# GPS.net
KiCad netlist of a schematic drawn in Altium Designer
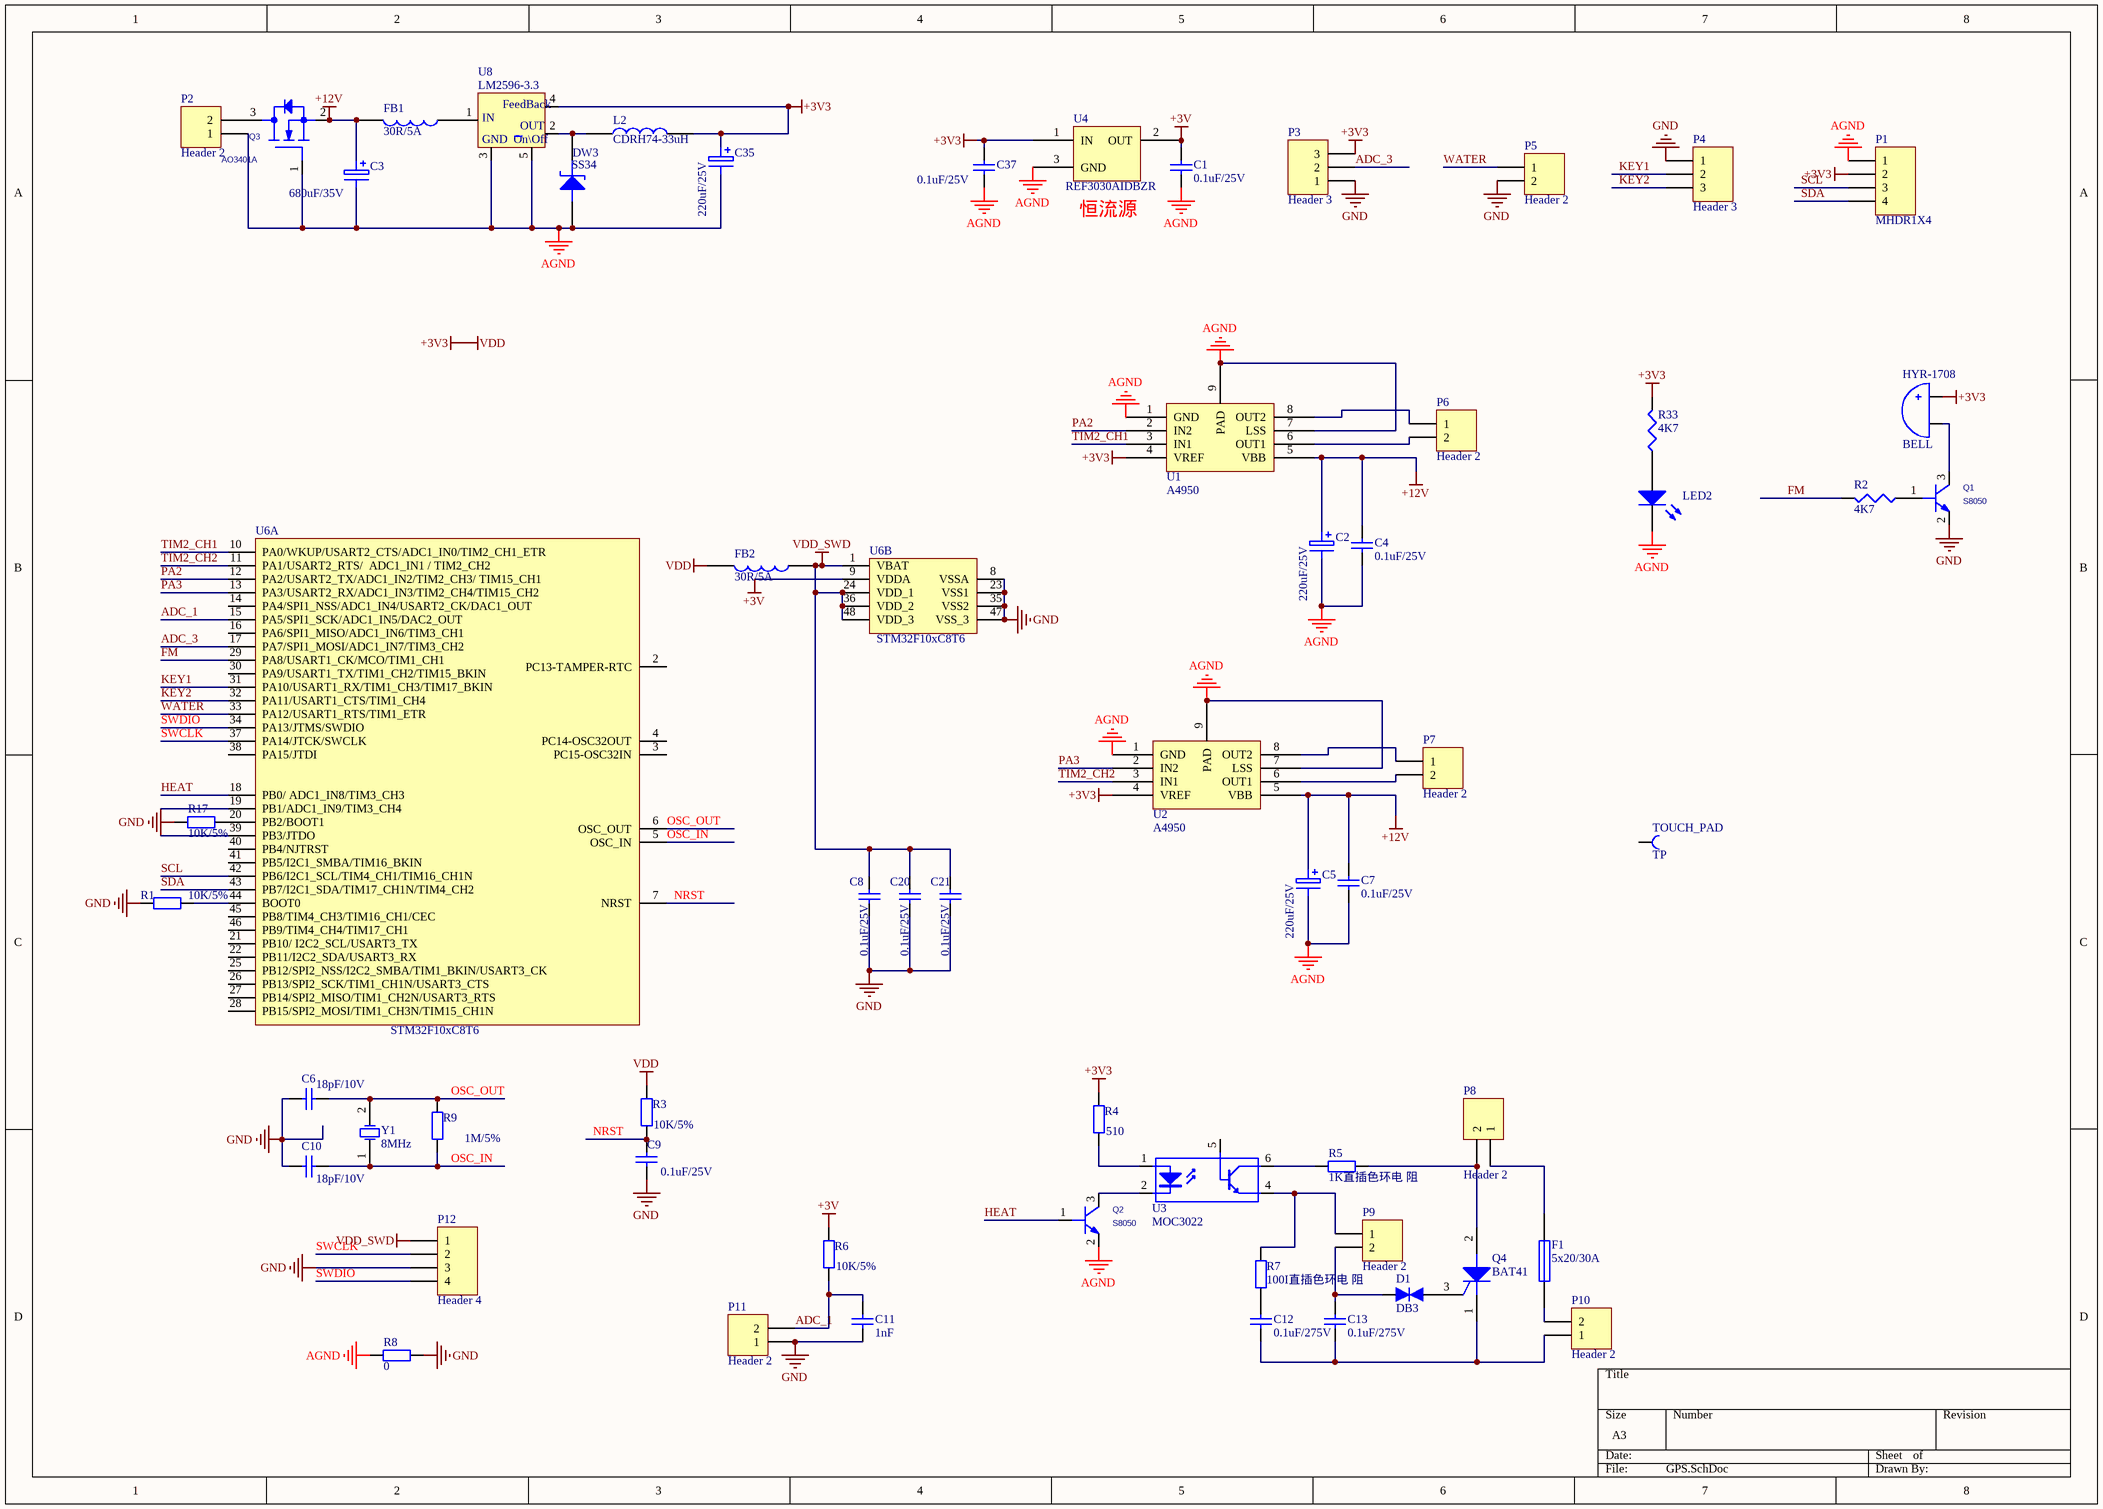
[diagram p0: GPS.SchDoc]

(export (version "E")
  (design (tool "Eeschema 10.0.6"))
  (components
    (comp (ref "C1")
      (value "0.1uF/25V")
      (footprint "0603C")
      (description "Capacitor")
      (fields (field (name "PUBLISHER") "Altium Limited"))
      (libsource (lib "Miscellaneous Devices") (part "Cap"))
    )
    (comp (ref "C2") (value "220uF/25V") (footprint "CAP 2.5*6.3*11.2") (libsource (lib "*") (part "E01")))
    (comp (ref "C3") (value "680uF/35V") (footprint "CAP 5.0*10*16") (libsource (lib "*") (part "E01")))
    (comp (ref "C4")
      (value "0.1uF/25V")
      (footprint "0603C")
      (description "Capacitor")
      (fields (field (name "PUBLISHER") "Altium Limited"))
      (libsource (lib "Miscellaneous Devices") (part "Cap"))
    )
    (comp (ref "C5") (value "220uF/25V") (footprint "CAP 2.5*6.3*11.2") (libsource (lib "*") (part "E01")))
    (comp (ref "C6")
      (value "18pF/10V")
      (footprint "0603C")
      (description "Capacitor")
      (fields (field (name "PUBLISHER") "Altium Limited"))
      (libsource (lib "Miscellaneous Devices") (part "Cap"))
    )
    (comp (ref "C7")
      (value "0.1uF/25V")
      (footprint "0603C")
      (description "Capacitor")
      (fields (field (name "PUBLISHER") "Altium Limited"))
      (libsource (lib "Miscellaneous Devices") (part "Cap"))
    )
    (comp (ref "C8")
      (value "0.1uF/25V")
      (footprint "0603C")
      (description "Capacitor")
      (fields (field (name "PUBLISHER") "Altium Limited"))
      (libsource (lib "Miscellaneous Devices") (part "Cap"))
    )
    (comp (ref "C9")
      (value "0.1uF/25V")
      (footprint "0603c")
      (description "Capacitor")
      (fields (field (name "PUBLISHER") "Altium Limited"))
      (libsource (lib "Miscellaneous Devices") (part "Cap"))
    )
    (comp (ref "C10")
      (value "18pF/10V")
      (footprint "0603c")
      (description "Capacitor")
      (fields (field (name "PUBLISHER") "Altium Limited"))
      (libsource (lib "Miscellaneous Devices") (part "Cap"))
    )
    (comp (ref "C11")
      (value "1nF")
      (footprint "0603C")
      (description "Capacitor")
      (fields (field (name "PUBLISHER") "Altium Limited"))
      (libsource (lib "Miscellaneous Devices") (part "Cap"))
    )
    (comp (ref "C12")
      (value "0.1uF/275V")
      (footprint "CBB 10*12*8")
      (description "Capacitor")
      (fields (field (name "PUBLISHER") "Altium Limited"))
      (libsource (lib "Miscellaneous Devices") (part "Cap"))
    )
    (comp (ref "C13")
      (value "0.1uF/275V")
      (footprint "CBB 10*12*8")
      (description "Capacitor")
      (fields (field (name "PUBLISHER") "Altium Limited"))
      (libsource (lib "Miscellaneous Devices") (part "Cap"))
    )
    (comp (ref "C20")
      (value "0.1uF/25V")
      (footprint "0603C")
      (description "Capacitor")
      (fields (field (name "PUBLISHER") "Altium Limited"))
      (libsource (lib "Miscellaneous Devices") (part "Cap"))
    )
    (comp (ref "C21")
      (value "0.1uF/25V")
      (footprint "0603C")
      (description "Capacitor")
      (fields (field (name "PUBLISHER") "Altium Limited"))
      (libsource (lib "Miscellaneous Devices") (part "Cap"))
    )
    (comp (ref "C35") (value "220uF/25V") (footprint "CAP 2.5*6.3*11.2") (libsource (lib "*") (part "E01")))
    (comp (ref "C37")
      (value "0.1uF/25V")
      (footprint "0603C")
      (description "Capacitor")
      (fields (field (name "PUBLISHER") "Altium Limited"))
      (libsource (lib "Miscellaneous Devices") (part "Cap"))
    )
    (comp (ref "D1")
      (value "DB3")
      (footprint "DO-35")
      (libsource (lib "Schlib_20110825") (part "ESD9M5.0S-DTVS105"))
    )
    (comp (ref "DW3")
      (value "SS34")
      (footprint "SMA")
      (description "Zener Diode")
      (libsource (lib "MySchlib") (part "ZENER2"))
    )
    (comp (ref "F1")
      (value "5x20/30A")
      (footprint "FU BLX-A")
      (description "Fuse")
      (fields (field (name "PUBLISHER") "Altium Limited"))
      (libsource (lib "Miscellaneous Devices") (part "Fuse 1"))
    )
    (comp (ref "FB1") (value "30R/5A") (footprint "L 0805") (libsource (lib "*") (part "INDUCTOR1")))
    (comp (ref "FB2") (value "30R/5A") (footprint "L 0805") (libsource (lib "*") (part "INDUCTOR1")))
    (comp (ref "HYR-1708")
      (value "BELL")
      (footprint "BEEP 5x9x5.5")
      (description "Bell")
      (libsource (lib "*") (part "BELL"))
    )
    (comp (ref "L2") (value "CDRH74-33uH") (footprint "CDRH74") (libsource (lib "*") (part "INDUCTOR1")))
    (comp (ref "LED2")
      (value "~")
      (footprint "LED 0805R")
      (description "Typical INFRARED GaAs LED")
      (fields (field (name "PUBLISHER") "Altium Limited"))
      (libsource (lib "Miscellaneous Devices") (part "LED0"))
    )
    (comp (ref "P1")
      (value "MHDR1X4")
      (footprint "MX 1.25-LS-4P")
      (description "Header, 4-Pin")
      (fields (field (name "PUBLISHER") "Altium Limited"))
      (libsource (lib "Miscellaneous Connectors") (part "MHDR1X4"))
    )
    (comp (ref "P2")
      (value "Header 2")
      (footprint "VH3.96-LI-2P")
      (description "Header, 2-Pin")
      (fields (field (name "PUBLISHER") "Altium Limited"))
      (libsource (lib "") (part "Header 2_2"))
    )
    (comp (ref "P3")
      (value "Header 3")
      (footprint "XH2.54-LI-3P")
      (description "Header, 3-Pin")
      (fields (field (name "PUBLISHER") "Altium Limited"))
      (libsource (lib "Miscellaneous Connectors") (part "Header 3"))
    )
    (comp (ref "P4")
      (value "Header 3")
      (footprint "MX 1.25-LS-3P")
      (description "Header, 3-Pin")
      (fields (field (name "PUBLISHER") "Altium Limited"))
      (libsource (lib "") (part "Header 3_1"))
    )
    (comp (ref "P5")
      (value "Header 2")
      (footprint "PH2.0-LS-2P")
      (description "Header, 2-Pin")
      (fields (field (name "PUBLISHER") "Altium Limited"))
      (libsource (lib "") (part "Header 2_1"))
    )
    (comp (ref "P6")
      (value "Header 2")
      (footprint "XH2.54-LI-2P")
      (description "Header, 2-Pin")
      (fields (field (name "PUBLISHER") "Altium Limited"))
      (libsource (lib "") (part "Header 2_1"))
    )
    (comp (ref "P7")
      (value "Header 2")
      (footprint "XH2.54-LI-2P")
      (description "Header, 2-Pin")
      (fields (field (name "PUBLISHER") "Altium Limited"))
      (libsource (lib "") (part "Header 2_1"))
    )
    (comp (ref "P8")
      (value "Header 2")
      (footprint "KF2EDGK5.08-LI-2P")
      (description "Header, 2-Pin")
      (fields (field (name "PUBLISHER") "Altium Limited"))
      (libsource (lib "") (part "Header 2_1"))
    )
    (comp (ref "P9")
      (value "Header 2")
      (footprint "VH3.96-LI-2P")
      (description "Header, 2-Pin")
      (fields (field (name "PUBLISHER") "Altium Limited"))
      (libsource (lib "") (part "Header 2_1"))
    )
    (comp (ref "P10")
      (value "Header 2")
      (footprint "KF2EDGK5.08-LI-2P")
      (description "Header, 2-Pin")
      (fields (field (name "PUBLISHER") "Altium Limited"))
      (libsource (lib "Miscellaneous Connectors") (part "Header 2"))
    )
    (comp (ref "P11")
      (value "Header 2")
      (footprint "XH2.54-LI-2P")
      (description "Header, 2-Pin")
      (fields (field (name "PUBLISHER") "Altium Limited"))
      (libsource (lib "") (part "Header 2_2"))
    )
    (comp (ref "P12")
      (value "Header 4")
      (footprint "HDR1X4")
      (description "Header, 4-Pin")
      (fields (field (name "PUBLISHER") "Altium Limited"))
      (libsource (lib "Miscellaneous Connectors") (part "Header 4"))
    )
    (comp (ref "Q1") (value "S8050") (footprint "SOT23-3") (libsource (lib "*") (part "2N1069_1")))
    (comp (ref "Q2") (value "S8050") (footprint "SOT23-3") (libsource (lib "*") (part "2N1069_1")))
    (comp (ref "Q3") (value "AO3401A") (footprint "SOT23-3M") (libsource (lib "Ground_Lock") (part "NMOS")))
    (comp (ref "Q4")
      (value "BAT41")
      (footprint "TOP-3")
      (description "Silicon Controlled Rectifier")
      (fields (field (name "PUBLISHER") "Altium Limited"))
      (libsource (lib "Miscellaneous Devices") (part "SCR"))
    )
    (comp (ref "R1")
      (value "10K/5%")
      (footprint "0603r")
      (description "Resistor")
      (fields (field (name "PUBLISHER") "Altium Limited"))
      (libsource (lib "") (part "Res2_1"))
    )
    (comp (ref "R2")
      (value "4K7")
      (footprint "0603R")
      (libsource (lib "ZWLIntegrated_Library") (part "RES1"))
    )
    (comp (ref "R3")
      (value "10K/5%")
      (footprint "0603r")
      (description "Resistor")
      (fields (field (name "PUBLISHER") "Altium Limited"))
      (libsource (lib "Miscellaneous Devices") (part "Res2"))
    )
    (comp (ref "R4")
      (value "510")
      (footprint "0603r")
      (description "Resistor")
      (fields (field (name "PUBLISHER") "Altium Limited"))
      (libsource (lib "Miscellaneous Devices") (part "Res2"))
    )
    (comp (ref "R5")
      (value "1K直插色环电 阻")
      (footprint "RS 1W")
      (description "Resistor")
      (fields (field (name "PUBLISHER") "Altium Limited"))
      (libsource (lib "") (part "Res2_1"))
    )
    (comp (ref "R6")
      (value "10K/5%")
      (footprint "0603r")
      (description "Resistor")
      (fields (field (name "PUBLISHER") "Altium Limited"))
      (libsource (lib "Miscellaneous Devices") (part "Res2"))
    )
    (comp (ref "R7")
      (value "100I直插色环电 阻")
      (footprint "RS 1W")
      (description "Resistor")
      (fields (field (name "PUBLISHER") "Altium Limited"))
      (libsource (lib "") (part "Res2_2"))
    )
    (comp (ref "R8")
      (value "0")
      (footprint "R 0805_M")
      (description "Resistor")
      (fields (field (name "PUBLISHER") "Altium Limited"))
      (libsource (lib "") (part "Res2_1"))
    )
    (comp (ref "R9")
      (value "1M/5%")
      (footprint "0603R")
      (description "Resistor")
      (fields (field (name "PUBLISHER") "Altium Limited"))
      (libsource (lib "Miscellaneous Devices") (part "Res2"))
    )
    (comp (ref "R17")
      (value "10K/5%")
      (footprint "0603r")
      (description "Resistor")
      (fields (field (name "PUBLISHER") "Altium Limited"))
      (libsource (lib "") (part "Res2_1"))
    )
    (comp (ref "R33")
      (value "4K7")
      (footprint "0603R")
      (libsource (lib "ZWLIntegrated_Library") (part "RES1"))
    )
    (comp (ref "TOUCH_PAD")
      (value "TP")
      (footprint "SRP12-34-25-P")
      (description "TEST_3P")
      (libsource (lib "stm32") (part "TOUCH_PAD"))
    )
    (comp (ref "U1")
      (value "A4950")
      (footprint "SOIC_8_EP")
      (libsource (lib "Schlib_20110825") (part "A4950"))
    )
    (comp (ref "U2")
      (value "A4950")
      (footprint "SOIC_8_EP")
      (libsource (lib "Schlib_20110825") (part "A4950"))
    )
    (comp (ref "U3")
      (value "MOC3022")
      (footprint "DIP6-300")
      (description "5 Pin Mini Flat Pack Optocoupler")
      (fields (field (name "PUBLISHER") "Altium Limited"))
      (libsource (lib "Miscellaneous Devices") (part "Optoisolator2"))
    )
    (comp (ref "U4")
      (value "REF3030AIDBZR")
      (footprint "SOT23-3N")
      (libsource (lib "Schlib1") (part "REF3012"))
    )
    (comp (ref "U6")
      (value "STM32F10xC8T6")
      (footprint "LQFP48 7X7_N")
      (libsource (lib "Myself_1") (part "STM32F100C8T6"))
    )
    (comp (ref "U8") (value "LM2596-3.3") (footprint "TO263-5A") (libsource (lib "*") (part "LM2576")))
    (comp (ref "Y1")
      (value "8MHz")
      (footprint "OSC 5032-2P")
      (description "Crystal Oscillator")
      (fields (field (name "PUBLISHER") "Altium Limited"))
      (libsource (lib "Miscellaneous Devices") (part "XTAL"))
    )
  )
  (nets
    (net (code "1") (name "+3V") (class "Default")
      (node (ref "C1") (pin "1") (pinfunction "1_1") (pintype "passive"))
      (node (ref "R6") (pin "2") (pinfunction "2_2") (pintype "passive"))
      (node (ref "U4") (pin "2") (pinfunction "OUT_2") (pintype "passive"))
      (node (ref "U6") (pin "9") (pinfunction "VDDA_9") (pintype "passive"))
    )
    (net (code "2") (name "+3V3") (class "Default")
      (node (ref "C35") (pin "1") (pintype "passive"))
      (node (ref "C37") (pin "1") (pinfunction "1_1") (pintype "passive"))
      (node (ref "FB2") (pin "1") (pinfunction "1_1") (pintype "passive"))
      (node (ref "HYR-1708") (pin "1") (pinfunction "A_1") (pintype "passive"))
      (node (ref "L2") (pin "1") (pinfunction "1_1") (pintype "passive"))
      (node (ref "P1") (pin "2") (pinfunction "2_2") (pintype "passive"))
      (node (ref "P3") (pin "3") (pinfunction "3_3") (pintype "passive"))
      (node (ref "R3") (pin "2") (pinfunction "2_2") (pintype "passive"))
      (node (ref "R33") (pin "2") (pinfunction "2_2") (pintype "passive"))
      (node (ref "R4") (pin "2") (pinfunction "2_2") (pintype "passive"))
      (node (ref "U1") (pin "4") (pinfunction "VREF_4") (pintype "passive"))
      (node (ref "U2") (pin "4") (pinfunction "VREF_4") (pintype "passive"))
      (node (ref "U4") (pin "1") (pinfunction "IN_1") (pintype "passive"))
      (node (ref "U8") (pin "4") (pintype "passive"))
    )
    (net (code "3") (name "+12V") (class "Default")
      (node (ref "C2") (pin "1") (pintype "passive"))
      (node (ref "C3") (pin "1") (pintype "passive"))
      (node (ref "C4") (pin "1") (pinfunction "1_1") (pintype "passive"))
      (node (ref "C5") (pin "1") (pintype "passive"))
      (node (ref "C7") (pin "1") (pinfunction "1_1") (pintype "passive"))
      (node (ref "FB1") (pin "1") (pinfunction "1_1") (pintype "passive"))
      (node (ref "Q3") (pin "2") (pinfunction "SOURCE_2") (pintype "passive"))
      (node (ref "U1") (pin "5") (pinfunction "VBB_5") (pintype "passive"))
      (node (ref "U2") (pin "5") (pinfunction "VBB_5") (pintype "passive"))
    )
    (net (code "4") (name "/ADC_1") (class "Default")
      (node (ref "C11") (pin "1") (pinfunction "1_1") (pintype "passive"))
      (node (ref "P11") (pin "2") (pinfunction "2_2") (pintype "passive"))
      (node (ref "R6") (pin "1") (pinfunction "1_1") (pintype "passive"))
      (node (ref "U6") (pin "15") (pinfunction "PA5/SPI1_SCK/ADC1_IN5/DAC2_OUT_15") (pintype "passive"))
    )
    (net (code "5") (name "/ADC_3") (class "Default")
      (node (ref "P3") (pin "2") (pinfunction "2_2") (pintype "passive"))
      (node (ref "U6") (pin "17") (pinfunction "PA7/SPI1_MOSI/ADC1_IN7/TIM3_CH2_17") (pintype "passive"))
    )
    (net (code "6") (name "/FM") (class "Default")
      (node (ref "R2") (pin "2") (pinfunction "2_2") (pintype "passive"))
      (node (ref "U6") (pin "29") (pinfunction "PA8/USART1_CK/MCO/TIM1_CH1_29") (pintype "passive"))
    )
    (net (code "7") (name "/HEAT") (class "Default")
      (node (ref "Q2") (pin "1") (pinfunction "B_1") (pintype "passive"))
      (node (ref "U6") (pin "18") (pinfunction "PB0/_ADC1_IN8/TIM3_CH3_18") (pintype "passive"))
    )
    (net (code "8") (name "/KEY1") (class "Default")
      (node (ref "P4") (pin "2") (pinfunction "2_2") (pintype "passive"))
      (node (ref "U6") (pin "31") (pinfunction "PA10/USART1_RX/TIM1_CH3/TIM17_BKIN_31") (pintype "passive"))
    )
    (net (code "9") (name "/KEY2") (class "Default")
      (node (ref "P4") (pin "3") (pinfunction "3_3") (pintype "passive"))
      (node (ref "U6") (pin "32") (pinfunction "PA11/USART1_CTS/TIM1_CH4_32") (pintype "passive"))
    )
    (net (code "10") (name "/NRST") (class "Default")
      (node (ref "C9") (pin "2") (pinfunction "2_2") (pintype "passive"))
      (node (ref "R3") (pin "1") (pinfunction "1_1") (pintype "passive"))
      (node (ref "U6") (pin "7") (pinfunction "NRST_7") (pintype "passive"))
    )
    (net (code "11") (name "/OSC_IN") (class "Default")
      (node (ref "C10") (pin "2") (pinfunction "2_2") (pintype "passive"))
      (node (ref "R9") (pin "1") (pinfunction "1_1") (pintype "passive"))
      (node (ref "U6") (pin "5") (pinfunction "OSC_IN_5") (pintype "passive"))
      (node (ref "Y1") (pin "1") (pinfunction "OSC1_1") (pintype "passive"))
    )
    (net (code "12") (name "/OSC_OUT") (class "Default")
      (node (ref "C6") (pin "2") (pinfunction "2_2") (pintype "passive"))
      (node (ref "R9") (pin "2") (pinfunction "2_2") (pintype "passive"))
      (node (ref "U6") (pin "6") (pinfunction "OSC_OUT_6") (pintype "passive"))
      (node (ref "Y1") (pin "2") (pinfunction "OSC2_2") (pintype "passive"))
    )
    (net (code "13") (name "/PA2") (class "Default")
      (node (ref "U1") (pin "2") (pinfunction "IN2_2") (pintype "passive"))
      (node (ref "U6") (pin "12") (pinfunction "PA2/USART2_TX/ADC1_IN2/TIM2_CH3/_TIM15_CH1_12") (pintype "passive"))
    )
    (net (code "14") (name "/PA3") (class "Default")
      (node (ref "U2") (pin "2") (pinfunction "IN2_2") (pintype "passive"))
      (node (ref "U6") (pin "13") (pinfunction "PA3/USART2_RX/ADC1_IN3/TIM2_CH4/TIM15_CH2_13") (pintype "passive"))
    )
    (net (code "15") (name "/SCL") (class "Default")
      (node (ref "P1") (pin "3") (pinfunction "3_3") (pintype "passive"))
      (node (ref "U6") (pin "42") (pinfunction "PB6/I2C1_SCL/TIM4_CH1/TIM16_CH1N_42") (pintype "passive"))
    )
    (net (code "16") (name "/SDA") (class "Default")
      (node (ref "P1") (pin "4") (pinfunction "4_4") (pintype "passive"))
      (node (ref "U6") (pin "43") (pinfunction "PB7/I2C1_SDA/TIM17_CH1N/TIM4_CH2_43") (pintype "passive"))
    )
    (net (code "17") (name "/SWCLK") (class "Default")
      (node (ref "P12") (pin "2") (pinfunction "2_2") (pintype "passive"))
      (node (ref "U6") (pin "37") (pinfunction "PA14/JTCK/SWCLK_37") (pintype "passive"))
    )
    (net (code "18") (name "/SWDIO") (class "Default")
      (node (ref "P12") (pin "4") (pinfunction "4_4") (pintype "passive"))
      (node (ref "U6") (pin "34") (pinfunction "PA13/JTMS/SWDIO_34") (pintype "passive"))
    )
    (net (code "19") (name "/TIM2_CH1") (class "Default")
      (node (ref "U1") (pin "3") (pinfunction "IN1_3") (pintype "passive"))
      (node (ref "U6") (pin "10") (pinfunction "PA0/WKUP/USART2_CTS/ADC1_IN0/TIM2_CH1_ETR_10") (pintype "passive"))
    )
    (net (code "20") (name "/TIM2_CH2") (class "Default")
      (node (ref "U2") (pin "3") (pinfunction "IN1_3") (pintype "passive"))
      (node (ref "U6") (pin "11") (pinfunction "PA1/USART2_RTS/__ADC1_IN1_/_TIM2_CH2_11") (pintype "passive"))
    )
    (net (code "21") (name "/WATER") (class "Default")
      (node (ref "P5") (pin "1") (pinfunction "1_1") (pintype "passive"))
      (node (ref "U6") (pin "33") (pinfunction "PA12/USART1_RTS/TIM1_ETR_33") (pintype "passive"))
    )
    (net (code "22") (name "AGND") (class "Default")
      (node (ref "C1") (pin "2") (pinfunction "2_2") (pintype "passive"))
      (node (ref "C2") (pin "2") (pintype "passive"))
      (node (ref "C3") (pin "2") (pintype "passive"))
      (node (ref "C35") (pin "2") (pintype "passive"))
      (node (ref "C37") (pin "2") (pinfunction "2_2") (pintype "passive"))
      (node (ref "C4") (pin "2") (pinfunction "2_2") (pintype "passive"))
      (node (ref "C5") (pin "2") (pintype "passive"))
      (node (ref "C7") (pin "2") (pinfunction "2_2") (pintype "passive"))
      (node (ref "DW3") (pin "1") (pinfunction "A_1") (pintype "passive"))
      (node (ref "LED2") (pin "2") (pinfunction "K_2") (pintype "passive"))
      (node (ref "P1") (pin "1") (pinfunction "1_1") (pintype "passive"))
      (node (ref "P2") (pin "1") (pinfunction "1_1") (pintype "passive"))
      (node (ref "Q2") (pin "2") (pinfunction "E_2") (pintype "passive"))
      (node (ref "Q3") (pin "1") (pinfunction "GATE_1") (pintype "passive"))
      (node (ref "R8") (pin "2") (pinfunction "2_2") (pintype "passive"))
      (node (ref "U1") (pin "1") (pinfunction "GND_1") (pintype "passive"))
      (node (ref "U1") (pin "7") (pinfunction "LSS_7") (pintype "passive"))
      (node (ref "U1") (pin "9") (pinfunction "PAD_9") (pintype "passive"))
      (node (ref "U2") (pin "1") (pinfunction "GND_1") (pintype "passive"))
      (node (ref "U2") (pin "7") (pinfunction "LSS_7") (pintype "passive"))
      (node (ref "U2") (pin "9") (pinfunction "PAD_9") (pintype "passive"))
      (node (ref "U4") (pin "3") (pinfunction "GND_3") (pintype "passive"))
      (node (ref "U8") (pin "3") (pintype "passive"))
      (node (ref "U8") (pin "5") (pintype "passive"))
    )
    (net (code "23") (name "GND") (class "Default")
      (node (ref "C10") (pin "1") (pinfunction "1_1") (pintype "passive"))
      (node (ref "C11") (pin "2") (pinfunction "2_2") (pintype "passive"))
      (node (ref "C20") (pin "2") (pinfunction "2_2") (pintype "passive"))
      (node (ref "C21") (pin "2") (pinfunction "2_2") (pintype "passive"))
      (node (ref "C6") (pin "1") (pinfunction "1_1") (pintype "passive"))
      (node (ref "C8") (pin "2") (pinfunction "2_2") (pintype "passive"))
      (node (ref "C9") (pin "1") (pinfunction "1_1") (pintype "passive"))
      (node (ref "P11") (pin "1") (pinfunction "1_1") (pintype "passive"))
      (node (ref "P12") (pin "3") (pinfunction "3_3") (pintype "passive"))
      (node (ref "P3") (pin "1") (pinfunction "1_1") (pintype "passive"))
      (node (ref "P4") (pin "1") (pinfunction "1_1") (pintype "passive"))
      (node (ref "P5") (pin "2") (pinfunction "2_2") (pintype "passive"))
      (node (ref "Q1") (pin "2") (pinfunction "E_2") (pintype "passive"))
      (node (ref "R1") (pin "2") (pinfunction "2_2") (pintype "passive"))
      (node (ref "R17") (pin "2") (pinfunction "2_2") (pintype "passive"))
      (node (ref "R8") (pin "1") (pinfunction "1_1") (pintype "passive"))
      (node (ref "U6") (pin "23") (pinfunction "VSS1_23") (pintype "passive"))
      (node (ref "U6") (pin "35") (pinfunction "VSS2_35") (pintype "passive"))
      (node (ref "U6") (pin "47") (pinfunction "VSS_3_47") (pintype "passive"))
      (node (ref "U6") (pin "8") (pinfunction "VSSA_8") (pintype "passive"))
    )
    (net (code "24") (name "Net-(C12-Pad1)") (class "Default")
      (node (ref "C12") (pin "1") (pinfunction "1_1") (pintype "passive"))
      (node (ref "R7") (pin "2") (pinfunction "2_2") (pintype "passive"))
    )
    (net (code "25") (name "Net-(D1-A)") (class "Default")
      (node (ref "C13") (pin "1") (pinfunction "1_1") (pintype "passive"))
      (node (ref "D1") (pin "1") (pinfunction "A_1") (pintype "passive"))
      (node (ref "P9") (pin "2") (pinfunction "2_2") (pintype "passive"))
    )
    (net (code "26") (name "Net-(D1-K)") (class "Default")
      (node (ref "D1") (pin "2") (pinfunction "K_2") (pintype "passive"))
      (node (ref "Q4") (pin "3") (pinfunction "G_3") (pintype "passive"))
    )
    (net (code "27") (name "Net-(DW3-K)") (class "Default")
      (node (ref "DW3") (pin "2") (pinfunction "K_2") (pintype "passive"))
      (node (ref "L2") (pin "2") (pinfunction "2_2") (pintype "passive"))
      (node (ref "U8") (pin "2") (pintype "passive"))
    )
    (net (code "28") (name "Net-(F1-Pad1)") (class "Default")
      (node (ref "F1") (pin "1") (pinfunction "1_1") (pintype "passive"))
      (node (ref "P10") (pin "2") (pinfunction "2_2") (pintype "passive"))
    )
    (net (code "29") (name "Net-(F1-Pad2)") (class "Default")
      (node (ref "F1") (pin "2") (pinfunction "2_2") (pintype "passive"))
      (node (ref "P8") (pin "1") (pinfunction "1_1") (pintype "passive"))
    )
    (net (code "30") (name "Net-(FB1-Pad2)") (class "Default")
      (node (ref "FB1") (pin "2") (pinfunction "2_2") (pintype "passive"))
      (node (ref "U8") (pin "1") (pintype "passive"))
    )
    (net (code "31") (name "Net-(HYR-1708-B)") (class "Default")
      (node (ref "HYR-1708") (pin "2") (pinfunction "B_2") (pintype "passive"))
      (node (ref "Q1") (pin "3") (pinfunction "C_3") (pintype "passive"))
    )
    (net (code "32") (name "Net-(LED2-A)") (class "Default")
      (node (ref "LED2") (pin "1") (pinfunction "A_1") (pintype "passive"))
      (node (ref "R33") (pin "1") (pinfunction "1_1") (pintype "passive"))
    )
    (net (code "33") (name "Net-(Q1-B)") (class "Default")
      (node (ref "Q1") (pin "1") (pinfunction "B_1") (pintype "passive"))
      (node (ref "R2") (pin "1") (pinfunction "1_1") (pintype "passive"))
    )
    (net (code "34") (name "Net-(Q2-C)") (class "Default")
      (node (ref "Q2") (pin "3") (pinfunction "C_3") (pintype "passive"))
      (node (ref "U3") (pin "2") (pinfunction "K_2") (pintype "passive"))
    )
    (net (code "35") (name "Net-(Q3-DRAIN)") (class "Default")
      (node (ref "P2") (pin "2") (pinfunction "2_2") (pintype "passive"))
      (node (ref "Q3") (pin "3") (pinfunction "DRAIN_3") (pintype "passive"))
    )
    (net (code "36") (name "Net-(Q4-A)") (class "Default")
      (node (ref "P8") (pin "2") (pinfunction "2_2") (pintype "passive"))
      (node (ref "Q4") (pin "2") (pinfunction "A_2") (pintype "passive"))
      (node (ref "R5") (pin "1") (pinfunction "1_1") (pintype "passive"))
    )
    (net (code "37") (name "Net-(Q4-K)") (class "Default")
      (node (ref "C12") (pin "2") (pinfunction "2_2") (pintype "passive"))
      (node (ref "C13") (pin "2") (pinfunction "2_2") (pintype "passive"))
      (node (ref "P10") (pin "1") (pinfunction "1_1") (pintype "passive"))
      (node (ref "Q4") (pin "1") (pinfunction "K_1") (pintype "passive"))
    )
    (net (code "38") (name "Net-(U1-OUT1)") (class "Default")
      (node (ref "P6") (pin "2") (pinfunction "2_2") (pintype "passive"))
      (node (ref "U1") (pin "6") (pinfunction "OUT1_6") (pintype "passive"))
    )
    (net (code "39") (name "Net-(U1-OUT2)") (class "Default")
      (node (ref "P6") (pin "1") (pinfunction "1_1") (pintype "passive"))
      (node (ref "U1") (pin "8") (pinfunction "OUT2_8") (pintype "passive"))
    )
    (net (code "40") (name "Net-(U2-OUT1)") (class "Default")
      (node (ref "P7") (pin "2") (pinfunction "2_2") (pintype "passive"))
      (node (ref "U2") (pin "6") (pinfunction "OUT1_6") (pintype "passive"))
    )
    (net (code "41") (name "Net-(U2-OUT2)") (class "Default")
      (node (ref "P7") (pin "1") (pinfunction "1_1") (pintype "passive"))
      (node (ref "U2") (pin "8") (pinfunction "OUT2_8") (pintype "passive"))
    )
    (net (code "42") (name "Net-(U3-A)") (class "Default")
      (node (ref "R4") (pin "1") (pinfunction "1_1") (pintype "passive"))
      (node (ref "U3") (pin "1") (pinfunction "A_1") (pintype "passive"))
    )
    (net (code "43") (name "Net-(U3-C)") (class "Default")
      (node (ref "R5") (pin "2") (pinfunction "2_2") (pintype "passive"))
      (node (ref "U3") (pin "6") (pinfunction "C_6") (pintype "passive"))
    )
    (net (code "44") (name "Net-(U3-E)") (class "Default")
      (node (ref "P9") (pin "1") (pinfunction "1_1") (pintype "passive"))
      (node (ref "R7") (pin "1") (pinfunction "1_1") (pintype "passive"))
      (node (ref "U3") (pin "4") (pinfunction "E_4") (pintype "passive"))
    )
    (net (code "45") (name "Net-(U6A-BOOT0)") (class "Default")
      (node (ref "R1") (pin "1") (pinfunction "1_1") (pintype "passive"))
      (node (ref "U6") (pin "44") (pinfunction "BOOT0_44") (pintype "passive"))
    )
    (net (code "46") (name "Net-(U6A-PB2{slash}BOOT1)") (class "Default")
      (node (ref "R17") (pin "1") (pinfunction "1_1") (pintype "passive"))
      (node (ref "U6") (pin "20") (pinfunction "PB2/BOOT1_20") (pintype "passive"))
    )
    (net (code "47") (name "VDD_SWD") (class "Default")
      (node (ref "C20") (pin "1") (pinfunction "1_1") (pintype "passive"))
      (node (ref "C21") (pin "1") (pinfunction "1_1") (pintype "passive"))
      (node (ref "C8") (pin "1") (pinfunction "1_1") (pintype "passive"))
      (node (ref "FB2") (pin "2") (pinfunction "2_2") (pintype "passive"))
      (node (ref "P12") (pin "1") (pinfunction "1_1") (pintype "passive"))
      (node (ref "U6") (pin "1") (pinfunction "VBAT_1") (pintype "passive"))
      (node (ref "U6") (pin "24") (pinfunction "VDD_1_24") (pintype "passive"))
      (node (ref "U6") (pin "36") (pinfunction "VDD_2_36") (pintype "passive"))
      (node (ref "U6") (pin "48") (pinfunction "VDD_3_48") (pintype "passive"))
    )
    (net (code "48") (name "unconnected-(TOUCH_PAD-Pad1)") (class "Default")
      (node (ref "TOUCH_PAD") (pin "1") (pinfunction "1_1") (pintype "passive"))
    )
    (net (code "49") (name "unconnected-(U3-B-Pad5)") (class "Default")
      (node (ref "U3") (pin "5") (pinfunction "B_5") (pintype "passive"))
    )
    (net (code "50") (name "unconnected-(U6A-PA4{slash}SPI1_NSS{slash}ADC1_IN4{slash}USART2_CK{slash}DAC1_OUT-Pad14)") (class "Default")
      (node (ref "U6") (pin "14") (pinfunction "PA4/SPI1_NSS/ADC1_IN4/USART2_CK/DAC1_OUT_14") (pintype "passive"))
    )
    (net (code "51") (name "unconnected-(U6A-PA6{slash}SPI1_MISO{slash}ADC1_IN6{slash}TIM3_CH1-Pad16)") (class "Default")
      (node (ref "U6") (pin "16") (pinfunction "PA6/SPI1_MISO/ADC1_IN6/TIM3_CH1_16") (pintype "passive"))
    )
    (net (code "52") (name "unconnected-(U6A-PA9{slash}USART1_TX{slash}TIM1_CH2{slash}TIM15_BKIN-Pad30)") (class "Default")
      (node (ref "U6") (pin "30") (pinfunction "PA9/USART1_TX/TIM1_CH2/TIM15_BKIN_30") (pintype "passive"))
    )
    (net (code "53") (name "unconnected-(U6A-PA15{slash}JTDI-Pad38)") (class "Default")
      (node (ref "U6") (pin "38") (pinfunction "PA15/JTDI_38") (pintype "passive"))
    )
    (net (code "54") (name "unconnected-(U6A-PB1{slash}ADC1_IN9{slash}TIM3_CH4-Pad19)") (class "Default")
      (node (ref "U6") (pin "19") (pinfunction "PB1/ADC1_IN9/TIM3_CH4_19") (pintype "passive"))
    )
    (net (code "55") (name "unconnected-(U6A-PB3{slash}JTDO-Pad39)") (class "Default")
      (node (ref "U6") (pin "39") (pinfunction "PB3/JTDO_39") (pintype "passive"))
    )
    (net (code "56") (name "unconnected-(U6A-PB4{slash}NJTRST-Pad40)") (class "Default")
      (node (ref "U6") (pin "40") (pinfunction "PB4/NJTRST_40") (pintype "passive"))
    )
    (net (code "57") (name "unconnected-(U6A-PB5{slash}I2C1_SMBA{slash}TIM16_BKIN-Pad41)") (class "Default")
      (node (ref "U6") (pin "41") (pinfunction "PB5/I2C1_SMBA/TIM16_BKIN_41") (pintype "passive"))
    )
    (net (code "58") (name "unconnected-(U6A-PB8{slash}TIM4_CH3{slash}TIM16_CH1{slash}CEC-Pad45)") (class "Default")
      (node (ref "U6") (pin "45") (pinfunction "PB8/TIM4_CH3/TIM16_CH1/CEC_45") (pintype "passive"))
    )
    (net (code "59") (name "unconnected-(U6A-PB9{slash}TIM4_CH4{slash}TIM17_CH1-Pad46)") (class "Default")
      (node (ref "U6") (pin "46") (pinfunction "PB9/TIM4_CH4/TIM17_CH1_46") (pintype "passive"))
    )
    (net (code "60") (name "unconnected-(U6A-PB10{slash}_I2C2_SCL{slash}USART3_TX-Pad21)") (class "Default")
      (node (ref "U6") (pin "21") (pinfunction "PB10/_I2C2_SCL/USART3_TX_21") (pintype "passive"))
    )
    (net (code "61") (name "unconnected-(U6A-PB11{slash}I2C2_SDA{slash}USART3_RX-Pad22)") (class "Default")
      (node (ref "U6") (pin "22") (pinfunction "PB11/I2C2_SDA/USART3_RX_22") (pintype "passive"))
    )
    (net (code "62") (name "unconnected-(U6A-PB12{slash}SPI2_NSS{slash}I2C2_SMBA{slash}TIM1_BKIN{slash}USART3_CK-Pad25)") (class "Default")
      (node (ref "U6") (pin "25") (pinfunction "PB12/SPI2_NSS/I2C2_SMBA/TIM1_BKIN/USART3_CK_25") (pintype "passive"))
    )
    (net (code "63") (name "unconnected-(U6A-PB13{slash}SPI2_SCK{slash}TIM1_CH1N{slash}USART3_CTS-Pad26)") (class "Default")
      (node (ref "U6") (pin "26") (pinfunction "PB13/SPI2_SCK/TIM1_CH1N/USART3_CTS_26") (pintype "passive"))
    )
    (net (code "64") (name "unconnected-(U6A-PB14{slash}SPI2_MISO{slash}TIM1_CH2N{slash}USART3_RTS-Pad27)") (class "Default")
      (node (ref "U6") (pin "27") (pinfunction "PB14/SPI2_MISO/TIM1_CH2N/USART3_RTS_27") (pintype "passive"))
    )
    (net (code "65") (name "unconnected-(U6A-PB15{slash}SPI2_MOSI{slash}TIM1_CH3N{slash}TIM15_CH1N-Pad28)") (class "Default")
      (node (ref "U6") (pin "28") (pinfunction "PB15/SPI2_MOSI/TIM1_CH3N/TIM15_CH1N_28") (pintype "passive"))
    )
    (net (code "66") (name "unconnected-(U6A-PC13-TAMPER-RTC-Pad2)") (class "Default")
      (node (ref "U6") (pin "2") (pinfunction "PC13-TAMPER-RTC_2") (pintype "passive"))
    )
    (net (code "67") (name "unconnected-(U6A-PC14-OSC32OUT-Pad4)") (class "Default")
      (node (ref "U6") (pin "4") (pinfunction "PC14-OSC32OUT_4") (pintype "passive"))
    )
    (net (code "68") (name "unconnected-(U6A-PC15-OSC32IN-Pad3)") (class "Default")
      (node (ref "U6") (pin "3") (pinfunction "PC15-OSC32IN_3") (pintype "passive"))
    )
  )
)
